# Pots.net
KiCad netlist of a schematic drawn in EAGLE
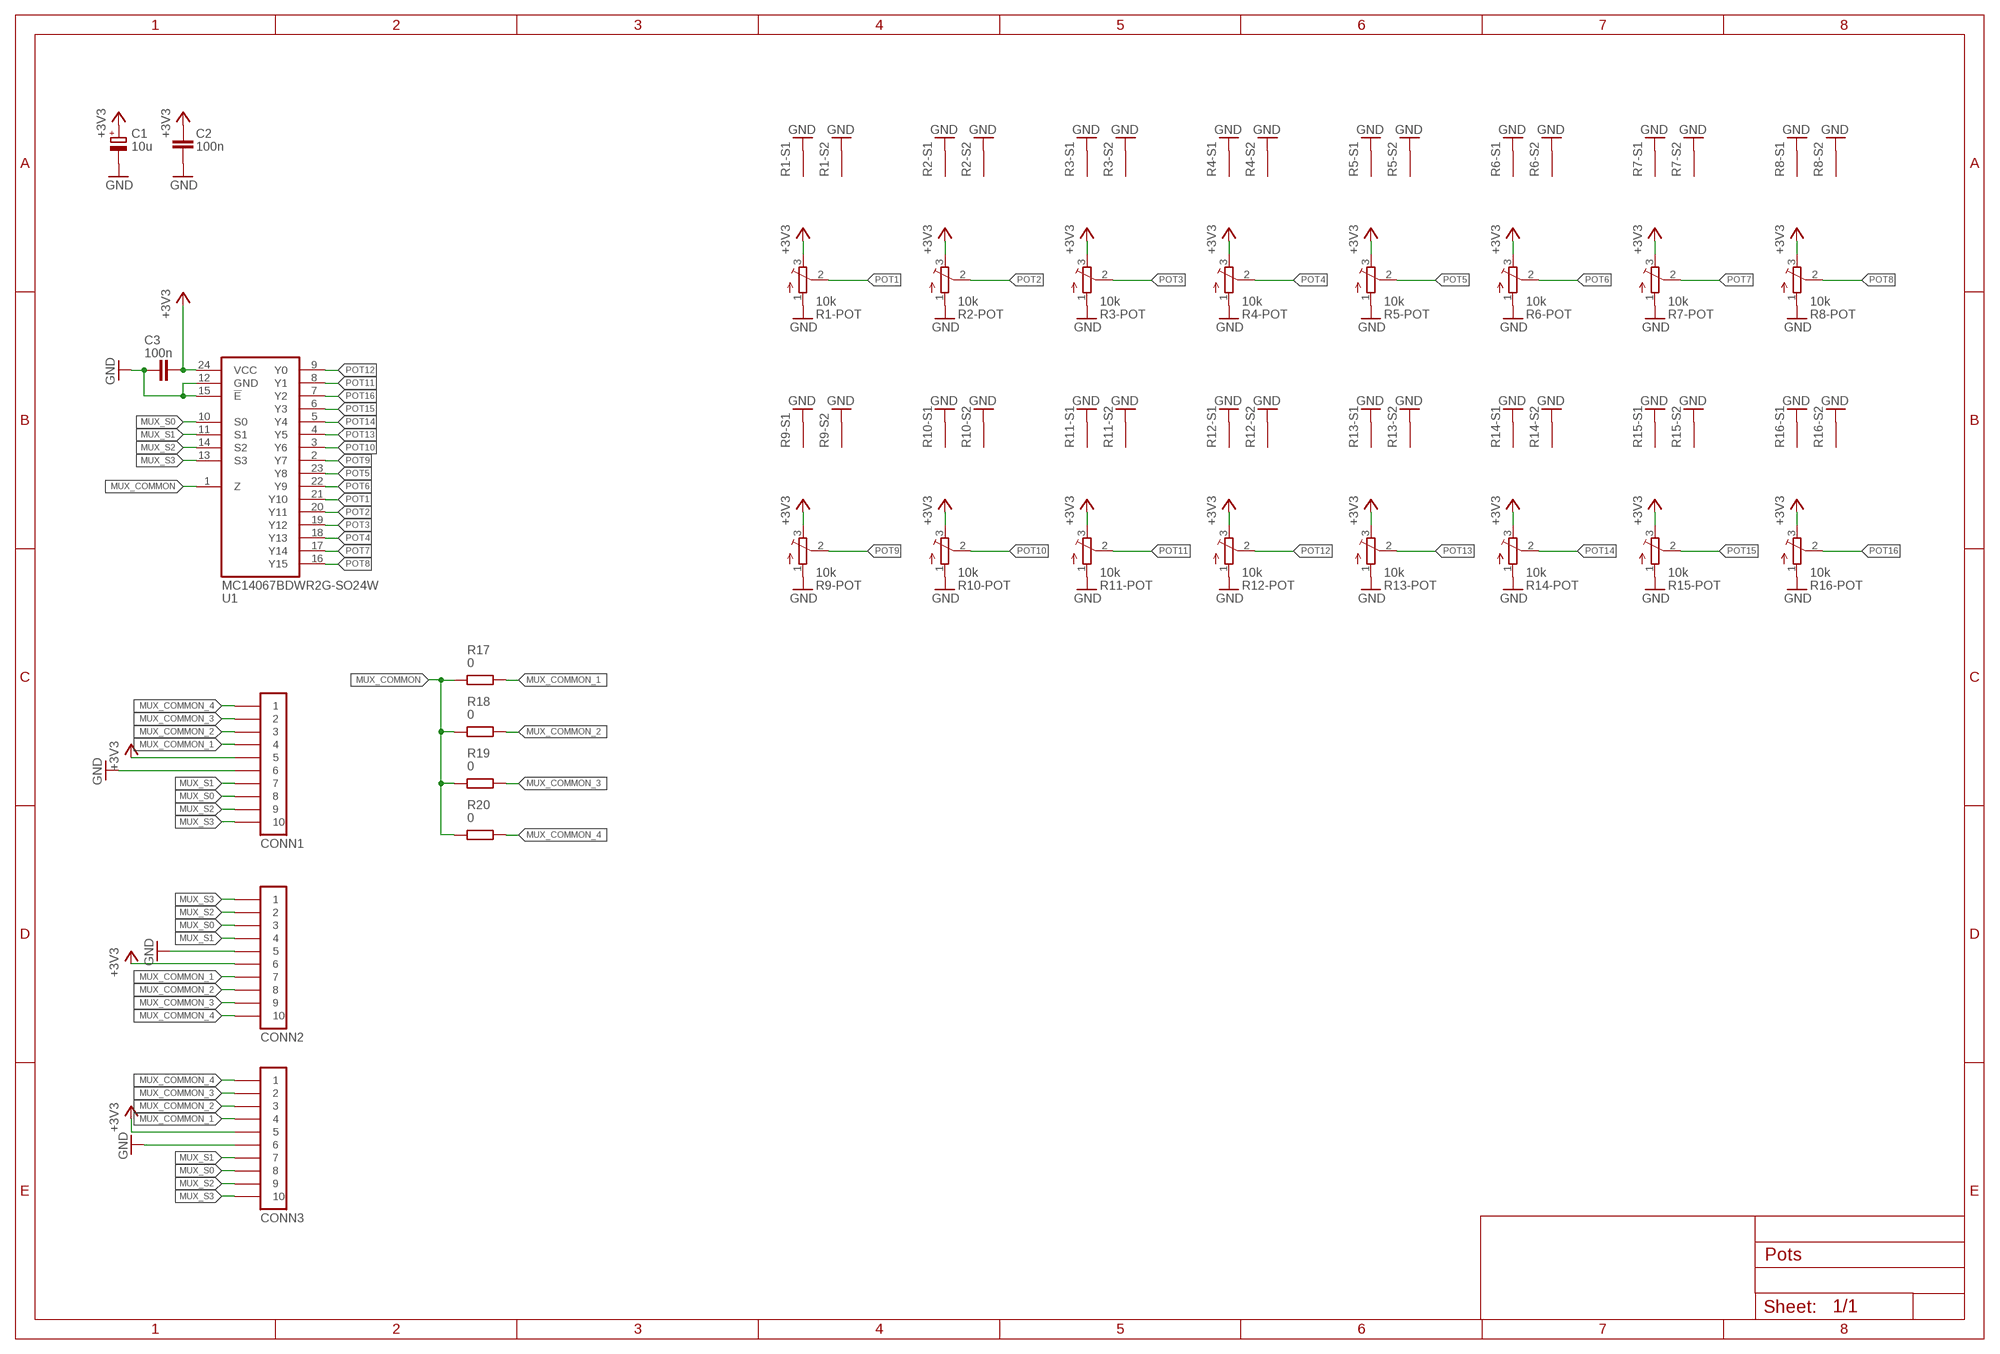
[diagram p0: schematic, sheet 1]

(export (version "E")
  (design (tool "Eeschema 10.0.6"))
  (components
    (comp (ref "C1")
      (value "10u")
      (footprint "eagle-import:C-TH-E-0401")
      (libsource (lib "eagle-import") (part "ELECTROLYTIC_CAPACITOR-C-TH-E-0401"))
    )
    (comp (ref "C2")
      (value "100n")
      (footprint "eagle-import:C0805")
      (libsource (lib "eagle-import") (part "CAPACITOR-0805"))
    )
    (comp (ref "C3")
      (value "100n")
      (footprint "eagle-import:C0805")
      (libsource (lib "eagle-import") (part "CAPACITOR-0805"))
    )
    (comp (ref "CONN1")
      (value "PINHD-1X10-FFC-1MM-Z")
      (footprint "eagle-import:MOLEX-52271-1079")
      (fields (field (name "MANUFACTURER") "Molex") (field (name "MPN") "52271-1079"))
      (libsource (lib "eagle-import") (part "PINHD-1X10-FFC-1MM-Z"))
    )
    (comp (ref "CONN2")
      (value "PINHD-1X10-FFC-1MM-Z")
      (footprint "eagle-import:MOLEX-52271-1079")
      (fields (field (name "MANUFACTURER") "Molex") (field (name "MPN") "52271-1079"))
      (libsource (lib "eagle-import") (part "PINHD-1X10-FFC-1MM-Z"))
    )
    (comp (ref "CONN3")
      (value "PINHD-1X10-FFC-1MM-Z")
      (footprint "eagle-import:MOLEX-52271-1079")
      (fields (field (name "MANUFACTURER") "Molex") (field (name "MPN") "52271-1079"))
      (libsource (lib "eagle-import") (part "PINHD-1X10-FFC-1MM-Z"))
    )
    (comp (ref "R1")
      (value "10k")
      (footprint "eagle-import:PTV09A-4025F-B103")
      (libsource (lib "eagle-import") (part "PTV09A-4025F-B103"))
    )
    (comp (ref "R2")
      (value "10k")
      (footprint "eagle-import:PTV09A-4025F-B103")
      (libsource (lib "eagle-import") (part "PTV09A-4025F-B103"))
    )
    (comp (ref "R3")
      (value "10k")
      (footprint "eagle-import:PTV09A-4025F-B103")
      (libsource (lib "eagle-import") (part "PTV09A-4025F-B103"))
    )
    (comp (ref "R4")
      (value "10k")
      (footprint "eagle-import:PTV09A-4025F-B103")
      (libsource (lib "eagle-import") (part "PTV09A-4025F-B103"))
    )
    (comp (ref "R5")
      (value "10k")
      (footprint "eagle-import:PTV09A-4025F-B103")
      (libsource (lib "eagle-import") (part "PTV09A-4025F-B103"))
    )
    (comp (ref "R6")
      (value "10k")
      (footprint "eagle-import:PTV09A-4025F-B103")
      (libsource (lib "eagle-import") (part "PTV09A-4025F-B103"))
    )
    (comp (ref "R7")
      (value "10k")
      (footprint "eagle-import:PTV09A-4025F-B103")
      (libsource (lib "eagle-import") (part "PTV09A-4025F-B103"))
    )
    (comp (ref "R8")
      (value "10k")
      (footprint "eagle-import:PTV09A-4025F-B103")
      (libsource (lib "eagle-import") (part "PTV09A-4025F-B103"))
    )
    (comp (ref "R9")
      (value "10k")
      (footprint "eagle-import:PTV09A-4025F-B103")
      (libsource (lib "eagle-import") (part "PTV09A-4025F-B103"))
    )
    (comp (ref "R10")
      (value "10k")
      (footprint "eagle-import:PTV09A-4025F-B103")
      (libsource (lib "eagle-import") (part "PTV09A-4025F-B103"))
    )
    (comp (ref "R11")
      (value "10k")
      (footprint "eagle-import:PTV09A-4025F-B103")
      (libsource (lib "eagle-import") (part "PTV09A-4025F-B103"))
    )
    (comp (ref "R12")
      (value "10k")
      (footprint "eagle-import:PTV09A-4025F-B103")
      (libsource (lib "eagle-import") (part "PTV09A-4025F-B103"))
    )
    (comp (ref "R13")
      (value "10k")
      (footprint "eagle-import:PTV09A-4025F-B103")
      (libsource (lib "eagle-import") (part "PTV09A-4025F-B103"))
    )
    (comp (ref "R14")
      (value "10k")
      (footprint "eagle-import:PTV09A-4025F-B103")
      (libsource (lib "eagle-import") (part "PTV09A-4025F-B103"))
    )
    (comp (ref "R15")
      (value "10k")
      (footprint "eagle-import:PTV09A-4025F-B103")
      (libsource (lib "eagle-import") (part "PTV09A-4025F-B103"))
    )
    (comp (ref "R16")
      (value "10k")
      (footprint "eagle-import:PTV09A-4025F-B103")
      (libsource (lib "eagle-import") (part "PTV09A-4025F-B103"))
    )
    (comp (ref "R17")
      (value "0")
      (footprint "eagle-import:R0805")
      (libsource (lib "eagle-import") (part "RESISTOR-0805"))
    )
    (comp (ref "R18")
      (value "0")
      (footprint "eagle-import:R0805")
      (libsource (lib "eagle-import") (part "RESISTOR-0805"))
    )
    (comp (ref "R19")
      (value "0")
      (footprint "eagle-import:R0805")
      (libsource (lib "eagle-import") (part "RESISTOR-0805"))
    )
    (comp (ref "R20")
      (value "0")
      (footprint "eagle-import:R0805")
      (libsource (lib "eagle-import") (part "RESISTOR-0805"))
    )
    (comp (ref "U1")
      (value "MC14067BDWR2G-SO24W")
      (footprint "eagle-import:SO24-W")
      (fields (field (name "MANUFACTURER") "ON Semiconductor") (field (name "MPN") "MC14067BDWR2G"))
      (libsource (lib "eagle-import") (part "MC14067BDWR2G-SO24W"))
    )
  )
  (nets
    (net (code "1") (name "+3V3") (class "Default")
      (node (ref "C1") (pin "+") (pinfunction "+_+") (pintype "passive"))
      (node (ref "C2") (pin "1") (pinfunction "1_1") (pintype "passive"))
      (node (ref "C3") (pin "2") (pinfunction "2_2") (pintype "passive"))
      (node (ref "CONN1") (pin "5") (pinfunction "5_5") (pintype "passive"))
      (node (ref "CONN2") (pin "6") (pinfunction "6_6") (pintype "passive"))
      (node (ref "CONN3") (pin "5") (pinfunction "5_5") (pintype "passive"))
      (node (ref "R1") (pin "3") (pinfunction "3_3") (pintype "passive"))
      (node (ref "R10") (pin "3") (pinfunction "3_3") (pintype "passive"))
      (node (ref "R11") (pin "3") (pinfunction "3_3") (pintype "passive"))
      (node (ref "R12") (pin "3") (pinfunction "3_3") (pintype "passive"))
      (node (ref "R13") (pin "3") (pinfunction "3_3") (pintype "passive"))
      (node (ref "R14") (pin "3") (pinfunction "3_3") (pintype "passive"))
      (node (ref "R15") (pin "3") (pinfunction "3_3") (pintype "passive"))
      (node (ref "R16") (pin "3") (pinfunction "3_3") (pintype "passive"))
      (node (ref "R2") (pin "3") (pinfunction "3_3") (pintype "passive"))
      (node (ref "R3") (pin "3") (pinfunction "3_3") (pintype "passive"))
      (node (ref "R4") (pin "3") (pinfunction "3_3") (pintype "passive"))
      (node (ref "R5") (pin "3") (pinfunction "3_3") (pintype "passive"))
      (node (ref "R6") (pin "3") (pinfunction "3_3") (pintype "passive"))
      (node (ref "R7") (pin "3") (pinfunction "3_3") (pintype "passive"))
      (node (ref "R8") (pin "3") (pinfunction "3_3") (pintype "passive"))
      (node (ref "R9") (pin "3") (pinfunction "3_3") (pintype "passive"))
      (node (ref "U1") (pin "24") (pinfunction "VCC_24") (pintype "passive"))
    )
    (net (code "2") (name "GND") (class "Default")
      (node (ref "C1") (pin "-") (pinfunction "-_-") (pintype "passive"))
      (node (ref "C2") (pin "2") (pinfunction "2_2") (pintype "passive"))
      (node (ref "C3") (pin "1") (pinfunction "1_1") (pintype "passive"))
      (node (ref "CONN1") (pin "6") (pinfunction "6_6") (pintype "passive"))
      (node (ref "CONN2") (pin "5") (pinfunction "5_5") (pintype "passive"))
      (node (ref "CONN3") (pin "6") (pinfunction "6_6") (pintype "passive"))
      (node (ref "R1") (pin "1") (pinfunction "1_1") (pintype "passive"))
      (node (ref "R1") (pin "S1") (pinfunction "S_S1") (pintype "passive"))
      (node (ref "R1") (pin "S2") (pinfunction "S_S2") (pintype "passive"))
      (node (ref "R10") (pin "1") (pinfunction "1_1") (pintype "passive"))
      (node (ref "R10") (pin "S1") (pinfunction "S_S1") (pintype "passive"))
      (node (ref "R10") (pin "S2") (pinfunction "S_S2") (pintype "passive"))
      (node (ref "R11") (pin "1") (pinfunction "1_1") (pintype "passive"))
      (node (ref "R11") (pin "S1") (pinfunction "S_S1") (pintype "passive"))
      (node (ref "R11") (pin "S2") (pinfunction "S_S2") (pintype "passive"))
      (node (ref "R12") (pin "1") (pinfunction "1_1") (pintype "passive"))
      (node (ref "R12") (pin "S1") (pinfunction "S_S1") (pintype "passive"))
      (node (ref "R12") (pin "S2") (pinfunction "S_S2") (pintype "passive"))
      (node (ref "R13") (pin "1") (pinfunction "1_1") (pintype "passive"))
      (node (ref "R13") (pin "S1") (pinfunction "S_S1") (pintype "passive"))
      (node (ref "R13") (pin "S2") (pinfunction "S_S2") (pintype "passive"))
      (node (ref "R14") (pin "1") (pinfunction "1_1") (pintype "passive"))
      (node (ref "R14") (pin "S1") (pinfunction "S_S1") (pintype "passive"))
      (node (ref "R14") (pin "S2") (pinfunction "S_S2") (pintype "passive"))
      (node (ref "R15") (pin "1") (pinfunction "1_1") (pintype "passive"))
      (node (ref "R15") (pin "S1") (pinfunction "S_S1") (pintype "passive"))
      (node (ref "R15") (pin "S2") (pinfunction "S_S2") (pintype "passive"))
      (node (ref "R16") (pin "1") (pinfunction "1_1") (pintype "passive"))
      (node (ref "R16") (pin "S1") (pinfunction "S_S1") (pintype "passive"))
      (node (ref "R16") (pin "S2") (pinfunction "S_S2") (pintype "passive"))
      (node (ref "R2") (pin "1") (pinfunction "1_1") (pintype "passive"))
      (node (ref "R2") (pin "S1") (pinfunction "S_S1") (pintype "passive"))
      (node (ref "R2") (pin "S2") (pinfunction "S_S2") (pintype "passive"))
      (node (ref "R3") (pin "1") (pinfunction "1_1") (pintype "passive"))
      (node (ref "R3") (pin "S1") (pinfunction "S_S1") (pintype "passive"))
      (node (ref "R3") (pin "S2") (pinfunction "S_S2") (pintype "passive"))
      (node (ref "R4") (pin "1") (pinfunction "1_1") (pintype "passive"))
      (node (ref "R4") (pin "S1") (pinfunction "S_S1") (pintype "passive"))
      (node (ref "R4") (pin "S2") (pinfunction "S_S2") (pintype "passive"))
      (node (ref "R5") (pin "1") (pinfunction "1_1") (pintype "passive"))
      (node (ref "R5") (pin "S1") (pinfunction "S_S1") (pintype "passive"))
      (node (ref "R5") (pin "S2") (pinfunction "S_S2") (pintype "passive"))
      (node (ref "R6") (pin "1") (pinfunction "1_1") (pintype "passive"))
      (node (ref "R6") (pin "S1") (pinfunction "S_S1") (pintype "passive"))
      (node (ref "R6") (pin "S2") (pinfunction "S_S2") (pintype "passive"))
      (node (ref "R7") (pin "1") (pinfunction "1_1") (pintype "passive"))
      (node (ref "R7") (pin "S1") (pinfunction "S_S1") (pintype "passive"))
      (node (ref "R7") (pin "S2") (pinfunction "S_S2") (pintype "passive"))
      (node (ref "R8") (pin "1") (pinfunction "1_1") (pintype "passive"))
      (node (ref "R8") (pin "S1") (pinfunction "S_S1") (pintype "passive"))
      (node (ref "R8") (pin "S2") (pinfunction "S_S2") (pintype "passive"))
      (node (ref "R9") (pin "1") (pinfunction "1_1") (pintype "passive"))
      (node (ref "R9") (pin "S1") (pinfunction "S_S1") (pintype "passive"))
      (node (ref "R9") (pin "S2") (pinfunction "S_S2") (pintype "passive"))
      (node (ref "U1") (pin "12") (pinfunction "GND_12") (pintype "passive"))
      (node (ref "U1") (pin "15") (pinfunction "~{E}_15") (pintype "input"))
    )
    (net (code "3") (name "MUX_COMMON") (class "Default")
      (node (ref "R17") (pin "1") (pinfunction "1_1") (pintype "passive"))
      (node (ref "R18") (pin "1") (pinfunction "1_1") (pintype "passive"))
      (node (ref "R19") (pin "1") (pinfunction "1_1") (pintype "passive"))
      (node (ref "R20") (pin "1") (pinfunction "1_1") (pintype "passive"))
      (node (ref "U1") (pin "1") (pinfunction "Z_1") (pintype "bidirectional"))
    )
    (net (code "4") (name "MUX_COMMON_1") (class "Default")
      (node (ref "CONN1") (pin "4") (pinfunction "4_4") (pintype "passive"))
      (node (ref "CONN2") (pin "7") (pinfunction "7_7") (pintype "passive"))
      (node (ref "CONN3") (pin "4") (pinfunction "4_4") (pintype "passive"))
      (node (ref "R17") (pin "2") (pinfunction "2_2") (pintype "passive"))
    )
    (net (code "5") (name "MUX_COMMON_2") (class "Default")
      (node (ref "CONN1") (pin "3") (pinfunction "3_3") (pintype "passive"))
      (node (ref "CONN2") (pin "8") (pinfunction "8_8") (pintype "passive"))
      (node (ref "CONN3") (pin "3") (pinfunction "3_3") (pintype "passive"))
      (node (ref "R18") (pin "2") (pinfunction "2_2") (pintype "passive"))
    )
    (net (code "6") (name "MUX_COMMON_3") (class "Default")
      (node (ref "CONN1") (pin "2") (pinfunction "2_2") (pintype "passive"))
      (node (ref "CONN2") (pin "9") (pinfunction "9_9") (pintype "passive"))
      (node (ref "CONN3") (pin "2") (pinfunction "2_2") (pintype "passive"))
      (node (ref "R19") (pin "2") (pinfunction "2_2") (pintype "passive"))
    )
    (net (code "7") (name "MUX_COMMON_4") (class "Default")
      (node (ref "CONN1") (pin "1") (pinfunction "1_1") (pintype "passive"))
      (node (ref "CONN2") (pin "10") (pinfunction "10_10") (pintype "passive"))
      (node (ref "CONN3") (pin "1") (pinfunction "1_1") (pintype "passive"))
      (node (ref "R20") (pin "2") (pinfunction "2_2") (pintype "passive"))
    )
    (net (code "8") (name "MUX_S0") (class "Default")
      (node (ref "CONN1") (pin "8") (pinfunction "8_8") (pintype "passive"))
      (node (ref "CONN2") (pin "3") (pinfunction "3_3") (pintype "passive"))
      (node (ref "CONN3") (pin "8") (pinfunction "8_8") (pintype "passive"))
      (node (ref "U1") (pin "10") (pinfunction "S0_10") (pintype "input"))
    )
    (net (code "9") (name "MUX_S1") (class "Default")
      (node (ref "CONN1") (pin "7") (pinfunction "7_7") (pintype "passive"))
      (node (ref "CONN2") (pin "4") (pinfunction "4_4") (pintype "passive"))
      (node (ref "CONN3") (pin "7") (pinfunction "7_7") (pintype "passive"))
      (node (ref "U1") (pin "11") (pinfunction "S1_11") (pintype "input"))
    )
    (net (code "10") (name "MUX_S2") (class "Default")
      (node (ref "CONN1") (pin "9") (pinfunction "9_9") (pintype "passive"))
      (node (ref "CONN2") (pin "2") (pinfunction "2_2") (pintype "passive"))
      (node (ref "CONN3") (pin "9") (pinfunction "9_9") (pintype "passive"))
      (node (ref "U1") (pin "14") (pinfunction "S2_14") (pintype "input"))
    )
    (net (code "11") (name "MUX_S3") (class "Default")
      (node (ref "CONN1") (pin "10") (pinfunction "10_10") (pintype "passive"))
      (node (ref "CONN2") (pin "1") (pinfunction "1_1") (pintype "passive"))
      (node (ref "CONN3") (pin "10") (pinfunction "10_10") (pintype "passive"))
      (node (ref "U1") (pin "13") (pinfunction "S3_13") (pintype "input"))
    )
    (net (code "12") (name "POT1") (class "Default")
      (node (ref "R1") (pin "2") (pinfunction "2_2") (pintype "passive"))
      (node (ref "U1") (pin "21") (pinfunction "Y10_21") (pintype "bidirectional"))
    )
    (net (code "13") (name "POT2") (class "Default")
      (node (ref "R2") (pin "2") (pinfunction "2_2") (pintype "passive"))
      (node (ref "U1") (pin "20") (pinfunction "Y11_20") (pintype "bidirectional"))
    )
    (net (code "14") (name "POT3") (class "Default")
      (node (ref "R3") (pin "2") (pinfunction "2_2") (pintype "passive"))
      (node (ref "U1") (pin "19") (pinfunction "Y12_19") (pintype "bidirectional"))
    )
    (net (code "15") (name "POT4") (class "Default")
      (node (ref "R4") (pin "2") (pinfunction "2_2") (pintype "passive"))
      (node (ref "U1") (pin "18") (pinfunction "Y13_18") (pintype "bidirectional"))
    )
    (net (code "16") (name "POT5") (class "Default")
      (node (ref "R5") (pin "2") (pinfunction "2_2") (pintype "passive"))
      (node (ref "U1") (pin "23") (pinfunction "Y8_23") (pintype "bidirectional"))
    )
    (net (code "17") (name "POT6") (class "Default")
      (node (ref "R6") (pin "2") (pinfunction "2_2") (pintype "passive"))
      (node (ref "U1") (pin "22") (pinfunction "Y9_22") (pintype "bidirectional"))
    )
    (net (code "18") (name "POT7") (class "Default")
      (node (ref "R7") (pin "2") (pinfunction "2_2") (pintype "passive"))
      (node (ref "U1") (pin "17") (pinfunction "Y14_17") (pintype "bidirectional"))
    )
    (net (code "19") (name "POT8") (class "Default")
      (node (ref "R8") (pin "2") (pinfunction "2_2") (pintype "passive"))
      (node (ref "U1") (pin "16") (pinfunction "Y15_16") (pintype "bidirectional"))
    )
    (net (code "20") (name "POT9") (class "Default")
      (node (ref "R9") (pin "2") (pinfunction "2_2") (pintype "passive"))
      (node (ref "U1") (pin "2") (pinfunction "Y7_2") (pintype "bidirectional"))
    )
    (net (code "21") (name "POT10") (class "Default")
      (node (ref "R10") (pin "2") (pinfunction "2_2") (pintype "passive"))
      (node (ref "U1") (pin "3") (pinfunction "Y6_3") (pintype "bidirectional"))
    )
    (net (code "22") (name "POT11") (class "Default")
      (node (ref "R11") (pin "2") (pinfunction "2_2") (pintype "passive"))
      (node (ref "U1") (pin "8") (pinfunction "Y1_8") (pintype "bidirectional"))
    )
    (net (code "23") (name "POT12") (class "Default")
      (node (ref "R12") (pin "2") (pinfunction "2_2") (pintype "passive"))
      (node (ref "U1") (pin "9") (pinfunction "Y0_9") (pintype "bidirectional"))
    )
    (net (code "24") (name "POT13") (class "Default")
      (node (ref "R13") (pin "2") (pinfunction "2_2") (pintype "passive"))
      (node (ref "U1") (pin "4") (pinfunction "Y5_4") (pintype "bidirectional"))
    )
    (net (code "25") (name "POT14") (class "Default")
      (node (ref "R14") (pin "2") (pinfunction "2_2") (pintype "passive"))
      (node (ref "U1") (pin "5") (pinfunction "Y4_5") (pintype "bidirectional"))
    )
    (net (code "26") (name "POT15") (class "Default")
      (node (ref "R15") (pin "2") (pinfunction "2_2") (pintype "passive"))
      (node (ref "U1") (pin "6") (pinfunction "Y3_6") (pintype "bidirectional"))
    )
    (net (code "27") (name "POT16") (class "Default")
      (node (ref "R16") (pin "2") (pinfunction "2_2") (pintype "passive"))
      (node (ref "U1") (pin "7") (pinfunction "Y2_7") (pintype "bidirectional"))
    )
  )
)
